# avr_hcsr04.net
KiCad netlist of a schematic drawn in EAGLE
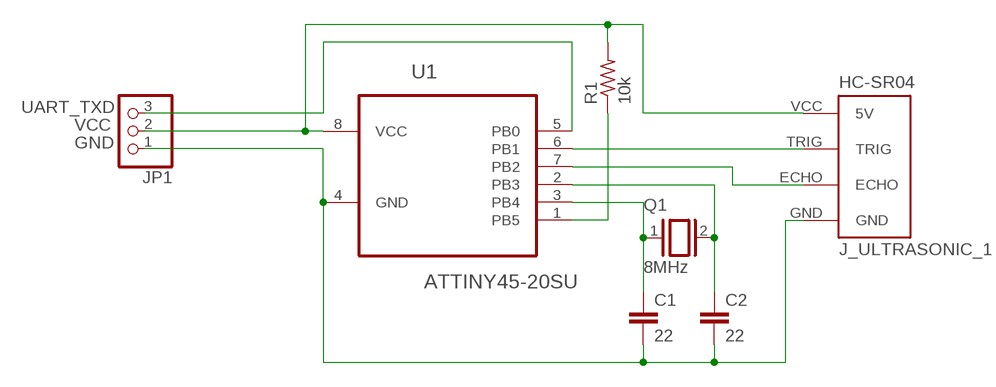
[diagram p0: schematic, sheet 1]

(export (version "E")
  (design (tool "Eeschema 10.0.6"))
  (components
    (comp (ref "C1")
      (value "22")
      (footprint "eagle-import:C025-024X044")
      (libsource (lib "eagle-import") (part "C-EU025-024X044"))
    )
    (comp (ref "C2")
      (value "22")
      (footprint "eagle-import:C025-024X044")
      (libsource (lib "eagle-import") (part "C-EU025-024X044"))
    )
    (comp (ref "JP1")
      (value "PINHD-1X3")
      (footprint "eagle-import:1X03")
      (libsource (lib "eagle-import") (part "PINHD-1X3"))
    )
    (comp (ref "J_ULTRASONIC_1")
      (value "HC-SR04")
      (footprint "eagle-import:HC-SR04_FOOTPRINT")
      (libsource (lib "eagle-import") (part "HC-SR04"))
    )
    (comp (ref "Q1")
      (value "8MHz")
      (footprint "eagle-import:Q")
      (libsource (lib "eagle-import") (part "XTAL"))
    )
    (comp (ref "R1")
      (value "10k")
      (footprint "eagle-import:0204_7")
      (libsource (lib "eagle-import") (part "R-US_0204/7"))
    )
    (comp (ref "U1")
      (value "ATTINY45-20SU")
      (footprint "eagle-import:SOIC127P798X216-8N")
      (libsource (lib "eagle-import") (part "ATTINY45-20SU"))
    )
  )
  (nets
    (net (code "1") (name "/GND") (class "Default")
      (node (ref "C1") (pin "2") (pinfunction "2_2") (pintype "passive"))
      (node (ref "C2") (pin "2") (pinfunction "2_2") (pintype "passive"))
      (node (ref "JP1") (pin "1") (pinfunction "1_1") (pintype "passive"))
      (node (ref "J_ULTRASONIC_1") (pin "GND") (pinfunction "GND_GND") (pintype "bidirectional"))
      (node (ref "U1") (pin "4") (pinfunction "GND_4") (pintype "passive"))
    )
    (net (code "2") (name "/UART_TXD") (class "Default")
      (node (ref "JP1") (pin "3") (pinfunction "3_3") (pintype "passive"))
      (node (ref "U1") (pin "5") (pinfunction "PB0_5") (pintype "bidirectional"))
    )
    (net (code "3") (name "/VCC") (class "Default")
      (node (ref "JP1") (pin "2") (pinfunction "2_2") (pintype "passive"))
      (node (ref "J_ULTRASONIC_1") (pin "VCC") (pinfunction "5V_VCC") (pintype "bidirectional"))
      (node (ref "R1") (pin "2") (pinfunction "2_2") (pintype "passive"))
      (node (ref "U1") (pin "8") (pinfunction "VCC_8") (pintype "power_in"))
    )
    (net (code "4") (name "Net-(U1-PB1)") (class "Default")
      (node (ref "J_ULTRASONIC_1") (pin "TRIG") (pinfunction "TRIG_TRIG") (pintype "bidirectional"))
      (node (ref "U1") (pin "6") (pinfunction "PB1_6") (pintype "bidirectional"))
    )
    (net (code "5") (name "Net-(U1-PB2)") (class "Default")
      (node (ref "J_ULTRASONIC_1") (pin "ECHO") (pinfunction "ECHO_ECHO") (pintype "bidirectional"))
      (node (ref "U1") (pin "7") (pinfunction "PB2_7") (pintype "bidirectional"))
    )
    (net (code "6") (name "Net-(U1-PB3)") (class "Default")
      (node (ref "C2") (pin "1") (pinfunction "1_1") (pintype "passive"))
      (node (ref "Q1") (pin "2") (pinfunction "2_2") (pintype "passive"))
      (node (ref "U1") (pin "2") (pinfunction "PB3_2") (pintype "bidirectional"))
    )
    (net (code "7") (name "Net-(U1-PB4)") (class "Default")
      (node (ref "C1") (pin "1") (pinfunction "1_1") (pintype "passive"))
      (node (ref "Q1") (pin "1") (pinfunction "1_1") (pintype "passive"))
      (node (ref "U1") (pin "3") (pinfunction "PB4_3") (pintype "bidirectional"))
    )
    (net (code "8") (name "Net-(U1-PB5)") (class "Default")
      (node (ref "R1") (pin "1") (pinfunction "1_1") (pintype "passive"))
      (node (ref "U1") (pin "1") (pinfunction "PB5_1") (pintype "bidirectional"))
    )
  )
)
